# 51.net
KiCad netlist of a schematic drawn in EasyEDA Pro
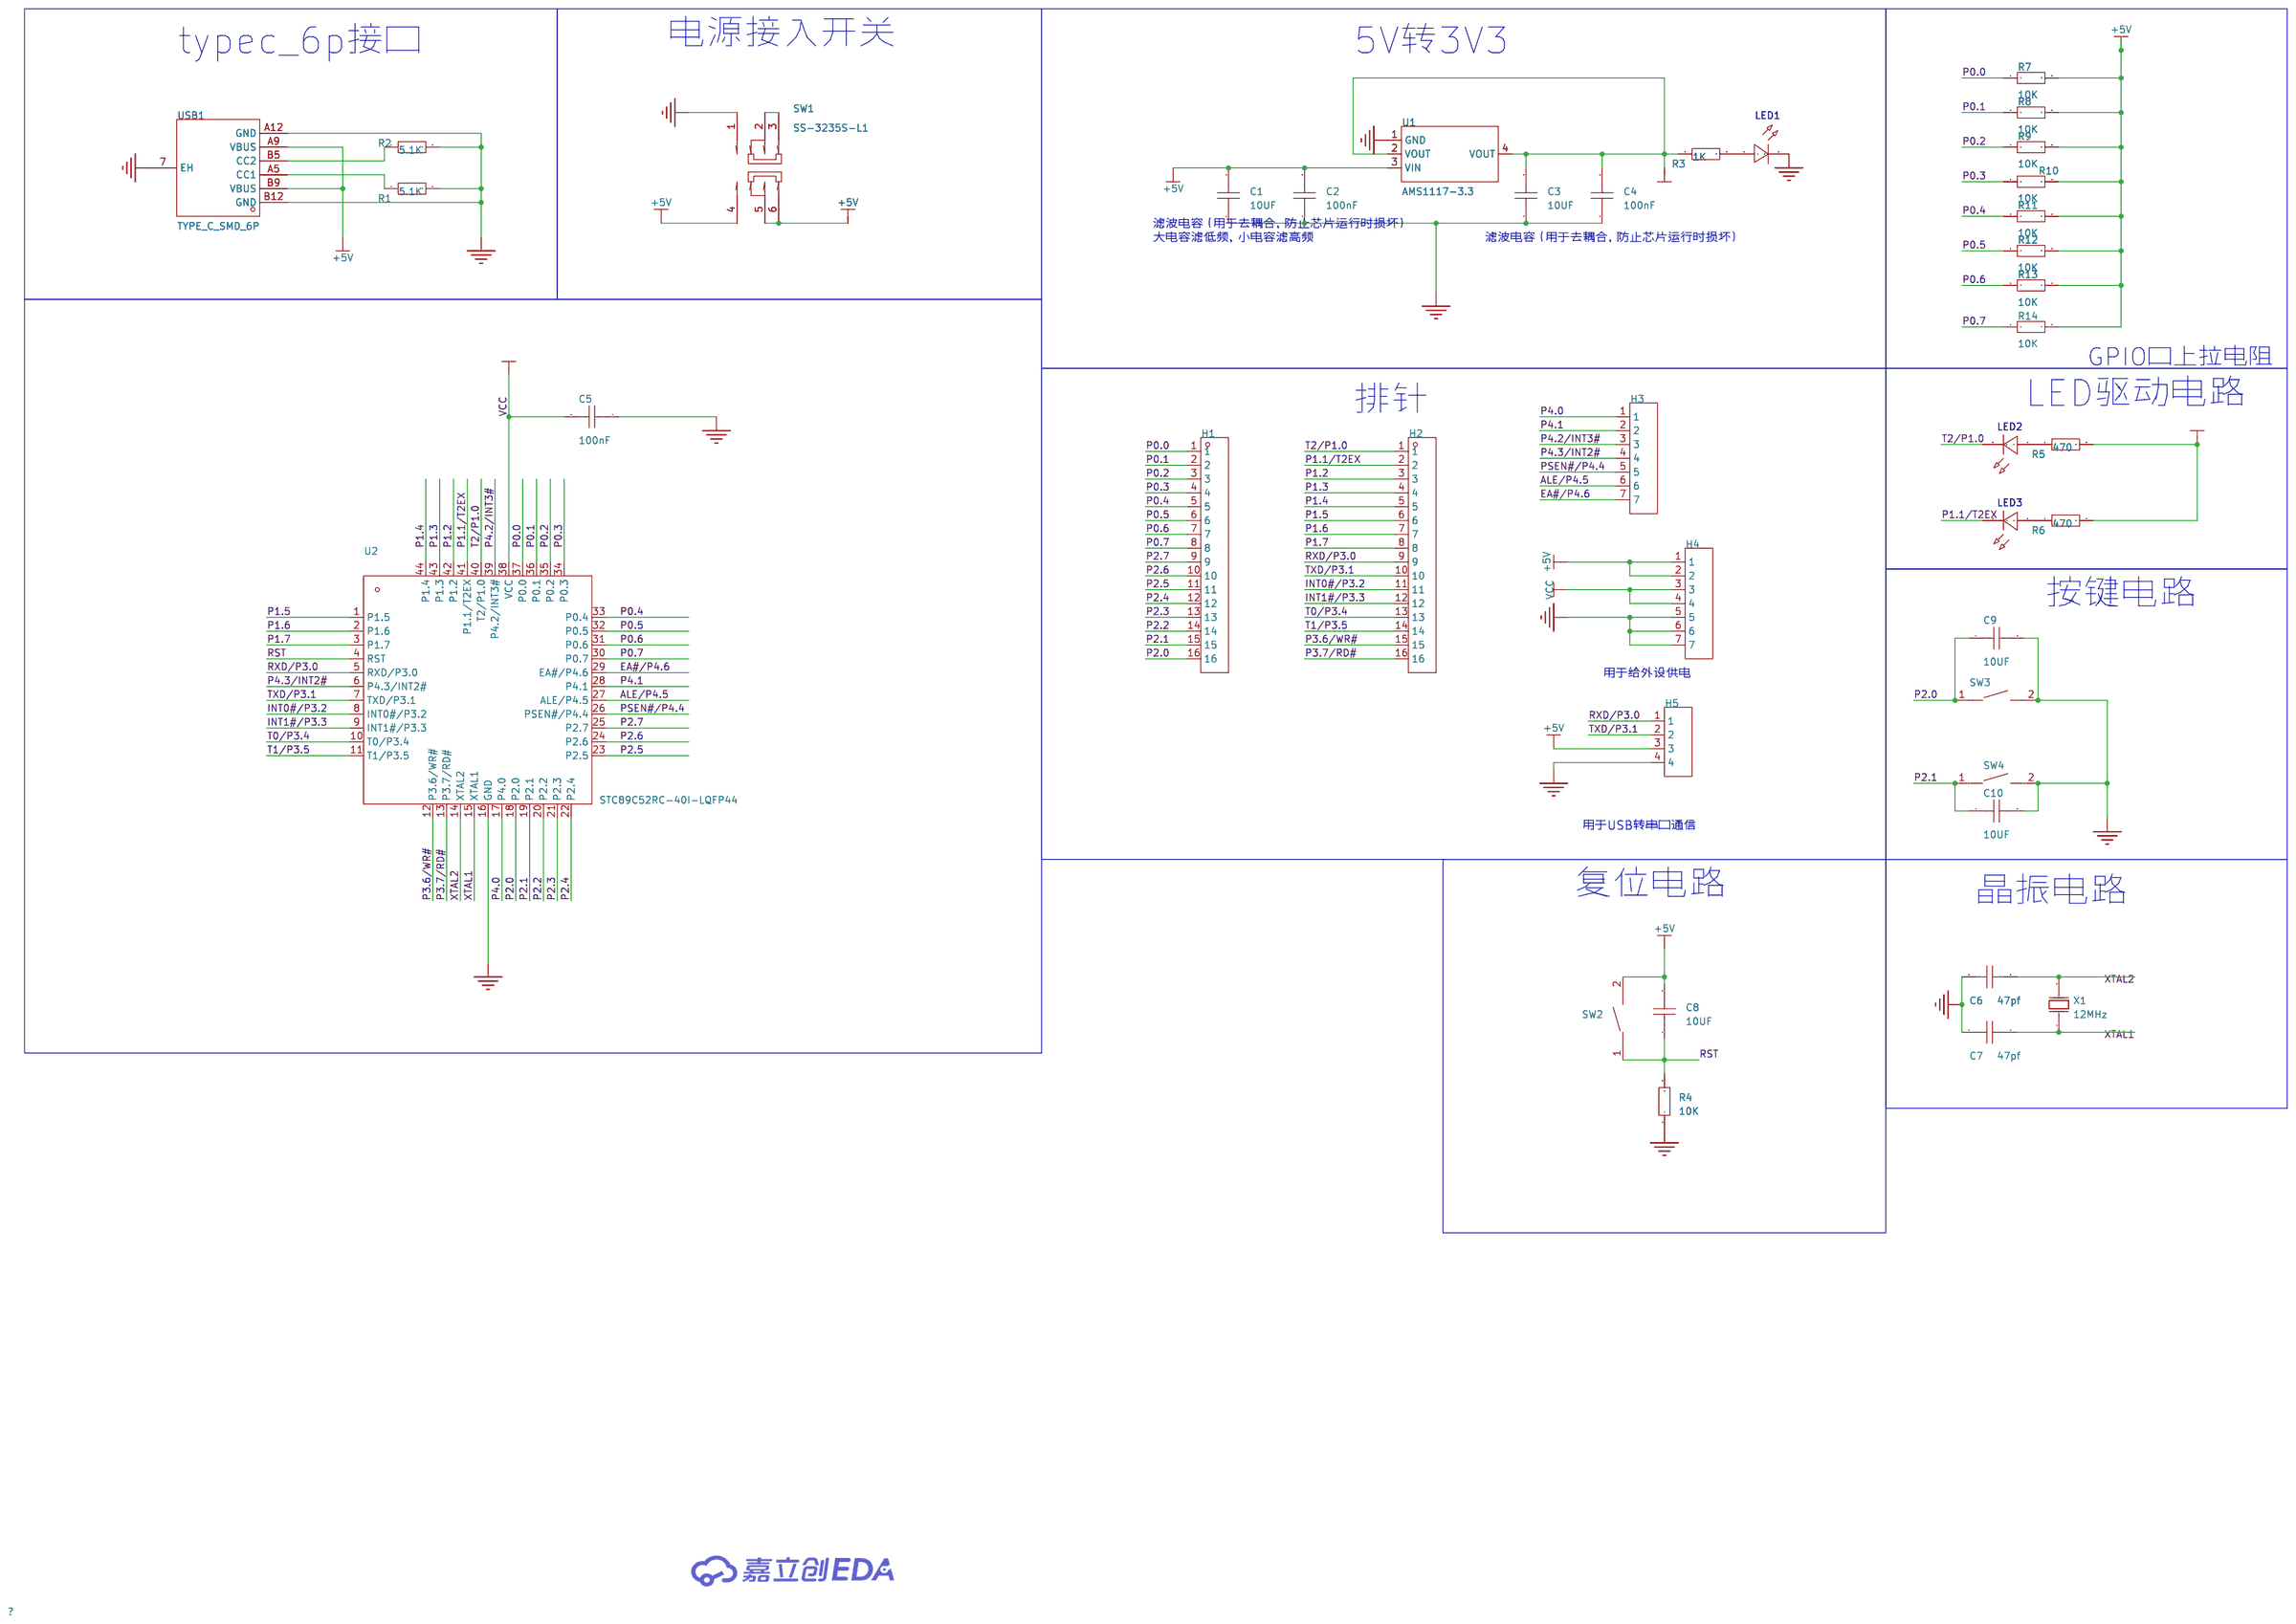
[diagram p0: schematic sheet]

(export (version "E")
  (design (tool "Eeschema 10.0.6"))
  (components
    (comp (ref "C1")
      (value "10UF")
      (footprint "easyedapro:C0805")
      (libsource (lib "easyedapro") (part "CapAcitance"))
    )
    (comp (ref "C2")
      (value "100nF")
      (footprint "easyedapro:C0805")
      (libsource (lib "easyedapro") (part "CapAcitance"))
    )
    (comp (ref "C3")
      (value "10UF")
      (footprint "easyedapro:C0805")
      (libsource (lib "easyedapro") (part "CapAcitance"))
    )
    (comp (ref "C4")
      (value "100nF")
      (footprint "easyedapro:C0805")
      (libsource (lib "easyedapro") (part "CapAcitance"))
    )
    (comp (ref "C5")
      (value "100nF")
      (footprint "easyedapro:C0805")
      (libsource (lib "easyedapro") (part "CapAcitance"))
    )
    (comp (ref "C6")
      (value "47pf")
      (footprint "easyedapro:C0805")
      (libsource (lib "easyedapro") (part "CapAcitance"))
    )
    (comp (ref "C7")
      (value "47pf")
      (footprint "easyedapro:C0805")
      (libsource (lib "easyedapro") (part "CapAcitance"))
    )
    (comp (ref "C8")
      (value "10UF")
      (footprint "easyedapro:C0805")
      (libsource (lib "easyedapro") (part "CapAcitance"))
    )
    (comp (ref "C9")
      (value "10UF")
      (footprint "easyedapro:C0805")
      (libsource (lib "easyedapro") (part "CapAcitance"))
    )
    (comp (ref "C10")
      (value "10UF")
      (footprint "easyedapro:C0805")
      (libsource (lib "easyedapro") (part "CapAcitance"))
    )
    (comp (ref "H1")
      (value "~")
      (footprint "easyedapro:HDR-TH_16P-P2.54-V-M")
      (libsource (lib "easyedapro") (part "HDR_2.54-1x16P"))
    )
    (comp (ref "H2")
      (value "~")
      (footprint "easyedapro:HDR-TH_16P-P2.54-V-M")
      (libsource (lib "easyedapro") (part "HDR_2.54-1x16P"))
    )
    (comp (ref "H3")
      (value "~")
      (footprint "easyedapro:HDR-TH_7P-P2.54-V-M")
      (libsource (lib "easyedapro") (part "PZ254V-11-07P"))
    )
    (comp (ref "H4")
      (value "~")
      (footprint "easyedapro:HDR-TH_7P-P2.54-V-M")
      (libsource (lib "easyedapro") (part "PZ254V-11-07P"))
    )
    (comp (ref "H5")
      (value "~")
      (footprint "easyedapro:HDR-TH_4P-P2.54-V-M")
      (libsource (lib "easyedapro") (part "PZ254V-11-04P"))
    )
    (comp (ref "LED1")
      (value "~")
      (footprint "easyedapro:LED_0805")
      (libsource (lib "easyedapro") (part "LED_G"))
    )
    (comp (ref "LED2")
      (value "~")
      (footprint "easyedapro:LED_0805")
      (libsource (lib "easyedapro") (part "LED_G"))
    )
    (comp (ref "LED3")
      (value "~")
      (footprint "easyedapro:LED_0805")
      (libsource (lib "easyedapro") (part "LED_G"))
    )
    (comp (ref "R1") (value "5.1K") (footprint "easyedapro:R0805") (libsource (lib "easyedapro") (part "电阻")))
    (comp (ref "R2") (value "5.1K") (footprint "easyedapro:R0805") (libsource (lib "easyedapro") (part "电阻")))
    (comp (ref "R3") (value "1K") (footprint "easyedapro:R0805") (libsource (lib "easyedapro") (part "电阻")))
    (comp (ref "R4") (value "10K") (footprint "easyedapro:R0805") (libsource (lib "easyedapro") (part "电阻")))
    (comp (ref "R5") (value "470") (footprint "easyedapro:R0805") (libsource (lib "easyedapro") (part "电阻")))
    (comp (ref "R6") (value "470") (footprint "easyedapro:R0805") (libsource (lib "easyedapro") (part "电阻")))
    (comp (ref "R7") (value "10K") (footprint "easyedapro:R0805") (libsource (lib "easyedapro") (part "电阻")))
    (comp (ref "R8") (value "10K") (footprint "easyedapro:R0805") (libsource (lib "easyedapro") (part "电阻")))
    (comp (ref "R9") (value "10K") (footprint "easyedapro:R0805") (libsource (lib "easyedapro") (part "电阻")))
    (comp (ref "R10") (value "10K") (footprint "easyedapro:R0805") (libsource (lib "easyedapro") (part "电阻")))
    (comp (ref "R11") (value "10K") (footprint "easyedapro:R0805") (libsource (lib "easyedapro") (part "电阻")))
    (comp (ref "R12") (value "10K") (footprint "easyedapro:R0805") (libsource (lib "easyedapro") (part "电阻")))
    (comp (ref "R13") (value "10K") (footprint "easyedapro:R0805") (libsource (lib "easyedapro") (part "电阻")))
    (comp (ref "R14") (value "10K") (footprint "easyedapro:R0805") (libsource (lib "easyedapro") (part "电阻")))
    (comp (ref "SW1")
      (value "SS-3235S-L1")
      (footprint "easyedapro:SW-SMD_SS-3235S-LX")
      (description "电路结构:双刀双掷;安装方式:卧贴;开关颜色:黑色;额定电流(DC):50mA;额定电压(DC):12V;额定电流(AC):50mA;额定电压(AC):12V;机械寿命:1万次;")
      (fields (field (name "Manufacturer") "XKB Connectivity(中国星坤)"))
      (libsource (lib "easyedapro") (part "SS-3235S-L1"))
    )
    (comp (ref "SW2")
      (value "轻触按键3*4*H")
      (footprint "easyedapro:SW-SMD_L4.0-W2.9-LS5.0")
      (libsource (lib "easyedapro") (part "轻触按键3*4*H"))
    )
    (comp (ref "SW3")
      (value "轻触按键3*4*H")
      (footprint "easyedapro:SW-SMD_L4.0-W2.9-LS5.0")
      (libsource (lib "easyedapro") (part "轻触按键3*4*H"))
    )
    (comp (ref "SW4")
      (value "轻触按键3*4*H")
      (footprint "easyedapro:SW-SMD_L4.0-W2.9-LS5.0")
      (libsource (lib "easyedapro") (part "轻触按键3*4*H"))
    )
    (comp (ref "U1")
      (value "AMS1117-3.3")
      (footprint "easyedapro:SOT-223-3_L6.5-W3.4-P2.30-LS7.0-BR")
      (description "输出类型:固定;工作电压:16V;输出电压:3.3V;输出电流:1A;电源纹波抑制比(PSRR):72dB@(120Hz);输出极性:正极;")
      (fields (field (name "Manufacturer") "AMS"))
      (libsource (lib "easyedapro") (part "AMS1117-3.3"))
    )
    (comp (ref "U2")
      (value "STC89C52RC-40I-LQFP44")
      (footprint "easyedapro:LQFP-44_L10.0-W10.0-P0.80-LS12.0-BL")
      (description "CPU内核:51系列;应用领域:-;")
      (fields (field (name "Manufacturer") "STC"))
      (libsource (lib "easyedapro") (part "STC89C52RC-40I_C8707"))
    )
    (comp (ref "USB1")
      (value "TYPE_C_SMD_6P")
      (footprint "easyedapro:TYPE-C-SMD_TYPE-C-6P")
      (libsource (lib "easyedapro") (part "TYPE_C_SMD_6P"))
    )
    (comp (ref "X1")
      (value "12MHz")
      (footprint "easyedapro:CRYSTAL-SMD_L7.0-W4.0-LS7.8")
      (description "频率:12MHz;常温频差:±15ppm;负载电容:20pF;频率稳定度:±30ppm;")
      (fields (field (name "Manufacturer Part") "12M 20PF 15PPM") (field (name "Manufacturer") "SST(索斯特)"))
      (libsource (lib "easyedapro") (part "12M 20PF 15PPM"))
    )
  )
  (nets
    (net (code "1") (name "+5V") (class "Default")
      (node (ref "C1") (pin "2") (pinfunction "2_2") (pintype "input"))
      (node (ref "C2") (pin "2") (pinfunction "2_2") (pintype "input"))
      (node (ref "C8") (pin "2") (pinfunction "2_2") (pintype "input"))
      (node (ref "H4") (pin "1") (pinfunction "1_1") (pintype "unspecified"))
      (node (ref "H4") (pin "2") (pinfunction "2_2") (pintype "unspecified"))
      (node (ref "H5") (pin "3") (pinfunction "3_3") (pintype "unspecified"))
      (node (ref "R10") (pin "2") (pinfunction "2_2") (pintype "input"))
      (node (ref "R11") (pin "2") (pinfunction "2_2") (pintype "input"))
      (node (ref "R12") (pin "2") (pinfunction "2_2") (pintype "input"))
      (node (ref "R13") (pin "2") (pinfunction "2_2") (pintype "input"))
      (node (ref "R14") (pin "2") (pinfunction "2_2") (pintype "input"))
      (node (ref "R7") (pin "2") (pinfunction "2_2") (pintype "input"))
      (node (ref "R8") (pin "2") (pinfunction "2_2") (pintype "input"))
      (node (ref "R9") (pin "2") (pinfunction "2_2") (pintype "input"))
      (node (ref "SW1") (pin "4") (pinfunction "4_4") (pintype "unspecified"))
      (node (ref "SW1") (pin "5") (pinfunction "5_5") (pintype "unspecified"))
      (node (ref "SW1") (pin "6") (pinfunction "6_6") (pintype "unspecified"))
      (node (ref "SW2") (pin "2") (pinfunction "2_2") (pintype "unspecified"))
      (node (ref "U1") (pin "3") (pinfunction "VIN_3") (pintype "unspecified"))
      (node (ref "USB1") (pin "A9") (pinfunction "VBUS_A9") (pintype "unspecified"))
      (node (ref "USB1") (pin "B9") (pinfunction "VBUS_B9") (pintype "unspecified"))
    )
    (net (code "2") (name "/ALE{slash}P4.5") (class "Default")
      (node (ref "H3") (pin "6") (pinfunction "6_6") (pintype "unspecified"))
      (node (ref "U2") (pin "27") (pinfunction "ALE/P4.5_27") (pintype "unspecified"))
    )
    (net (code "3") (name "/EA#{slash}P4.6") (class "Default")
      (node (ref "H3") (pin "7") (pinfunction "7_7") (pintype "unspecified"))
      (node (ref "U2") (pin "29") (pinfunction "EA#/P4.6_29") (pintype "unspecified"))
    )
    (net (code "4") (name "/INT0#{slash}P3.2") (class "Default")
      (node (ref "H2") (pin "11") (pinfunction "11_11") (pintype "input"))
      (node (ref "U2") (pin "8") (pinfunction "INT0#/P3.2_8") (pintype "unspecified"))
    )
    (net (code "5") (name "/INT1#{slash}P3.3") (class "Default")
      (node (ref "H2") (pin "12") (pinfunction "12_12") (pintype "input"))
      (node (ref "U2") (pin "9") (pinfunction "INT1#/P3.3_9") (pintype "unspecified"))
    )
    (net (code "6") (name "/P0.0") (class "Default")
      (node (ref "H1") (pin "1") (pinfunction "1_1") (pintype "input"))
      (node (ref "R7") (pin "1") (pinfunction "1_1") (pintype "input"))
      (node (ref "U2") (pin "37") (pinfunction "P0.0_37") (pintype "unspecified"))
    )
    (net (code "7") (name "/P0.1") (class "Default")
      (node (ref "H1") (pin "2") (pinfunction "2_2") (pintype "input"))
      (node (ref "R8") (pin "1") (pinfunction "1_1") (pintype "input"))
      (node (ref "U2") (pin "36") (pinfunction "P0.1_36") (pintype "unspecified"))
    )
    (net (code "8") (name "/P0.2") (class "Default")
      (node (ref "H1") (pin "3") (pinfunction "3_3") (pintype "input"))
      (node (ref "R9") (pin "1") (pinfunction "1_1") (pintype "input"))
      (node (ref "U2") (pin "35") (pinfunction "P0.2_35") (pintype "unspecified"))
    )
    (net (code "9") (name "/P0.3") (class "Default")
      (node (ref "H1") (pin "4") (pinfunction "4_4") (pintype "input"))
      (node (ref "R10") (pin "1") (pinfunction "1_1") (pintype "input"))
      (node (ref "U2") (pin "34") (pinfunction "P0.3_34") (pintype "unspecified"))
    )
    (net (code "10") (name "/P0.4") (class "Default")
      (node (ref "H1") (pin "5") (pinfunction "5_5") (pintype "input"))
      (node (ref "R11") (pin "1") (pinfunction "1_1") (pintype "input"))
      (node (ref "U2") (pin "33") (pinfunction "P0.4_33") (pintype "unspecified"))
    )
    (net (code "11") (name "/P0.5") (class "Default")
      (node (ref "H1") (pin "6") (pinfunction "6_6") (pintype "input"))
      (node (ref "R12") (pin "1") (pinfunction "1_1") (pintype "input"))
      (node (ref "U2") (pin "32") (pinfunction "P0.5_32") (pintype "unspecified"))
    )
    (net (code "12") (name "/P0.6") (class "Default")
      (node (ref "H1") (pin "7") (pinfunction "7_7") (pintype "input"))
      (node (ref "R13") (pin "1") (pinfunction "1_1") (pintype "input"))
      (node (ref "U2") (pin "31") (pinfunction "P0.6_31") (pintype "unspecified"))
    )
    (net (code "13") (name "/P0.7") (class "Default")
      (node (ref "H1") (pin "8") (pinfunction "8_8") (pintype "input"))
      (node (ref "R14") (pin "1") (pinfunction "1_1") (pintype "input"))
      (node (ref "U2") (pin "30") (pinfunction "P0.7_30") (pintype "unspecified"))
    )
    (net (code "14") (name "/P1.1{slash}T2EX") (class "Default")
      (node (ref "H2") (pin "2") (pinfunction "2_2") (pintype "input"))
      (node (ref "LED3") (pin "1") (pinfunction "C_1") (pintype "input"))
      (node (ref "U2") (pin "41") (pinfunction "P1.1/T2EX_41") (pintype "unspecified"))
    )
    (net (code "15") (name "/P1.2") (class "Default")
      (node (ref "H2") (pin "3") (pinfunction "3_3") (pintype "input"))
      (node (ref "U2") (pin "42") (pinfunction "P1.2_42") (pintype "unspecified"))
    )
    (net (code "16") (name "/P1.3") (class "Default")
      (node (ref "H2") (pin "4") (pinfunction "4_4") (pintype "input"))
      (node (ref "U2") (pin "43") (pinfunction "P1.3_43") (pintype "unspecified"))
    )
    (net (code "17") (name "/P1.4") (class "Default")
      (node (ref "H2") (pin "5") (pinfunction "5_5") (pintype "input"))
      (node (ref "U2") (pin "44") (pinfunction "P1.4_44") (pintype "unspecified"))
    )
    (net (code "18") (name "/P1.5") (class "Default")
      (node (ref "H2") (pin "6") (pinfunction "6_6") (pintype "input"))
      (node (ref "U2") (pin "1") (pinfunction "P1.5_1") (pintype "unspecified"))
    )
    (net (code "19") (name "/P1.6") (class "Default")
      (node (ref "H2") (pin "7") (pinfunction "7_7") (pintype "input"))
      (node (ref "U2") (pin "2") (pinfunction "P1.6_2") (pintype "unspecified"))
    )
    (net (code "20") (name "/P1.7") (class "Default")
      (node (ref "H2") (pin "8") (pinfunction "8_8") (pintype "input"))
      (node (ref "U2") (pin "3") (pinfunction "P1.7_3") (pintype "unspecified"))
    )
    (net (code "21") (name "/P2.0") (class "Default")
      (node (ref "C9") (pin "1") (pinfunction "1_1") (pintype "input"))
      (node (ref "H1") (pin "16") (pinfunction "16_16") (pintype "input"))
      (node (ref "SW3") (pin "1") (pinfunction "1_1") (pintype "unspecified"))
      (node (ref "U2") (pin "18") (pinfunction "P2.0_18") (pintype "unspecified"))
    )
    (net (code "22") (name "/P2.1") (class "Default")
      (node (ref "C10") (pin "1") (pinfunction "1_1") (pintype "input"))
      (node (ref "H1") (pin "15") (pinfunction "15_15") (pintype "input"))
      (node (ref "SW4") (pin "1") (pinfunction "1_1") (pintype "unspecified"))
      (node (ref "U2") (pin "19") (pinfunction "P2.1_19") (pintype "unspecified"))
    )
    (net (code "23") (name "/P2.2") (class "Default")
      (node (ref "H1") (pin "14") (pinfunction "14_14") (pintype "input"))
      (node (ref "U2") (pin "20") (pinfunction "P2.2_20") (pintype "unspecified"))
    )
    (net (code "24") (name "/P2.3") (class "Default")
      (node (ref "H1") (pin "13") (pinfunction "13_13") (pintype "input"))
      (node (ref "U2") (pin "21") (pinfunction "P2.3_21") (pintype "unspecified"))
    )
    (net (code "25") (name "/P2.4") (class "Default")
      (node (ref "H1") (pin "12") (pinfunction "12_12") (pintype "input"))
      (node (ref "U2") (pin "22") (pinfunction "P2.4_22") (pintype "unspecified"))
    )
    (net (code "26") (name "/P2.5") (class "Default")
      (node (ref "H1") (pin "11") (pinfunction "11_11") (pintype "input"))
      (node (ref "U2") (pin "23") (pinfunction "P2.5_23") (pintype "unspecified"))
    )
    (net (code "27") (name "/P2.6") (class "Default")
      (node (ref "H1") (pin "10") (pinfunction "10_10") (pintype "input"))
      (node (ref "U2") (pin "24") (pinfunction "P2.6_24") (pintype "unspecified"))
    )
    (net (code "28") (name "/P2.7") (class "Default")
      (node (ref "H1") (pin "9") (pinfunction "9_9") (pintype "input"))
      (node (ref "U2") (pin "25") (pinfunction "P2.7_25") (pintype "unspecified"))
    )
    (net (code "29") (name "/P3.6{slash}WR#") (class "Default")
      (node (ref "H2") (pin "15") (pinfunction "15_15") (pintype "input"))
      (node (ref "U2") (pin "12") (pinfunction "P3.6/WR#_12") (pintype "unspecified"))
    )
    (net (code "30") (name "/P3.7{slash}RD#") (class "Default")
      (node (ref "H2") (pin "16") (pinfunction "16_16") (pintype "input"))
      (node (ref "U2") (pin "13") (pinfunction "P3.7/RD#_13") (pintype "unspecified"))
    )
    (net (code "31") (name "/P4.0") (class "Default")
      (node (ref "H3") (pin "1") (pinfunction "1_1") (pintype "unspecified"))
      (node (ref "U2") (pin "17") (pinfunction "P4.0_17") (pintype "unspecified"))
    )
    (net (code "32") (name "/P4.1") (class "Default")
      (node (ref "H3") (pin "2") (pinfunction "2_2") (pintype "unspecified"))
      (node (ref "U2") (pin "28") (pinfunction "P4.1_28") (pintype "unspecified"))
    )
    (net (code "33") (name "/P4.2{slash}INT3#") (class "Default")
      (node (ref "H3") (pin "3") (pinfunction "3_3") (pintype "unspecified"))
      (node (ref "U2") (pin "39") (pinfunction "P4.2/INT3#_39") (pintype "unspecified"))
    )
    (net (code "34") (name "/P4.3{slash}INT2#") (class "Default")
      (node (ref "H3") (pin "4") (pinfunction "4_4") (pintype "unspecified"))
      (node (ref "U2") (pin "6") (pinfunction "P4.3/INT2#_6") (pintype "unspecified"))
    )
    (net (code "35") (name "/PSEN#{slash}P4.4") (class "Default")
      (node (ref "H3") (pin "5") (pinfunction "5_5") (pintype "unspecified"))
      (node (ref "U2") (pin "26") (pinfunction "PSEN#/P4.4_26") (pintype "unspecified"))
    )
    (net (code "36") (name "/RST") (class "Default")
      (node (ref "C8") (pin "1") (pinfunction "1_1") (pintype "input"))
      (node (ref "R4") (pin "2") (pinfunction "2_2") (pintype "input"))
      (node (ref "SW2") (pin "1") (pinfunction "1_1") (pintype "unspecified"))
      (node (ref "U2") (pin "4") (pinfunction "RST_4") (pintype "unspecified"))
    )
    (net (code "37") (name "/RXD{slash}P3.0") (class "Default")
      (node (ref "H2") (pin "9") (pinfunction "9_9") (pintype "input"))
      (node (ref "H5") (pin "1") (pinfunction "1_1") (pintype "unspecified"))
      (node (ref "U2") (pin "5") (pinfunction "RXD/P3.0_5") (pintype "unspecified"))
    )
    (net (code "38") (name "/T0{slash}P3.4") (class "Default")
      (node (ref "H2") (pin "13") (pinfunction "13_13") (pintype "input"))
      (node (ref "U2") (pin "10") (pinfunction "T0/P3.4_10") (pintype "unspecified"))
    )
    (net (code "39") (name "/T1{slash}P3.5") (class "Default")
      (node (ref "H2") (pin "14") (pinfunction "14_14") (pintype "input"))
      (node (ref "U2") (pin "11") (pinfunction "T1/P3.5_11") (pintype "unspecified"))
    )
    (net (code "40") (name "/T2{slash}P1.0") (class "Default")
      (node (ref "H2") (pin "1") (pinfunction "1_1") (pintype "input"))
      (node (ref "LED2") (pin "1") (pinfunction "C_1") (pintype "input"))
      (node (ref "U2") (pin "40") (pinfunction "T2/P1.0_40") (pintype "unspecified"))
    )
    (net (code "41") (name "/TXD{slash}P3.1") (class "Default")
      (node (ref "H2") (pin "10") (pinfunction "10_10") (pintype "input"))
      (node (ref "H5") (pin "2") (pinfunction "2_2") (pintype "unspecified"))
      (node (ref "U2") (pin "7") (pinfunction "TXD/P3.1_7") (pintype "unspecified"))
    )
    (net (code "42") (name "/XTAL1") (class "Default")
      (node (ref "C7") (pin "2") (pinfunction "2_2") (pintype "input"))
      (node (ref "U2") (pin "15") (pinfunction "XTAL1_15") (pintype "unspecified"))
      (node (ref "X1") (pin "1") (pinfunction "OSC1_1") (pintype "input"))
    )
    (net (code "43") (name "/XTAL2") (class "Default")
      (node (ref "C6") (pin "2") (pinfunction "2_2") (pintype "input"))
      (node (ref "U2") (pin "14") (pinfunction "XTAL2_14") (pintype "unspecified"))
      (node (ref "X1") (pin "2") (pinfunction "OSC2_2") (pintype "input"))
    )
    (net (code "44") (name "3V3") (class "Default")
      (node (ref "C3") (pin "2") (pinfunction "2_2") (pintype "input"))
      (node (ref "C4") (pin "2") (pinfunction "2_2") (pintype "input"))
      (node (ref "R3") (pin "1") (pinfunction "1_1") (pintype "input"))
      (node (ref "R5") (pin "2") (pinfunction "2_2") (pintype "input"))
      (node (ref "R6") (pin "2") (pinfunction "2_2") (pintype "input"))
      (node (ref "U1") (pin "2") (pinfunction "VOUT_2") (pintype "unspecified"))
      (node (ref "U1") (pin "4") (pinfunction "VOUT_4") (pintype "unspecified"))
    )
    (net (code "45") (name "GND") (class "Default")
      (node (ref "C1") (pin "1") (pinfunction "1_1") (pintype "input"))
      (node (ref "C10") (pin "2") (pinfunction "2_2") (pintype "input"))
      (node (ref "C2") (pin "1") (pinfunction "1_1") (pintype "input"))
      (node (ref "C3") (pin "1") (pinfunction "1_1") (pintype "input"))
      (node (ref "C4") (pin "1") (pinfunction "1_1") (pintype "input"))
      (node (ref "C5") (pin "1") (pinfunction "1_1") (pintype "input"))
      (node (ref "C6") (pin "1") (pinfunction "1_1") (pintype "input"))
      (node (ref "C7") (pin "1") (pinfunction "1_1") (pintype "input"))
      (node (ref "C9") (pin "2") (pinfunction "2_2") (pintype "input"))
      (node (ref "H4") (pin "5") (pinfunction "5_5") (pintype "unspecified"))
      (node (ref "H4") (pin "6") (pinfunction "6_6") (pintype "unspecified"))
      (node (ref "H4") (pin "7") (pinfunction "7_7") (pintype "unspecified"))
      (node (ref "H5") (pin "4") (pinfunction "4_4") (pintype "unspecified"))
      (node (ref "LED1") (pin "1") (pinfunction "C_1") (pintype "input"))
      (node (ref "R1") (pin "2") (pinfunction "2_2") (pintype "input"))
      (node (ref "R2") (pin "2") (pinfunction "2_2") (pintype "input"))
      (node (ref "R4") (pin "1") (pinfunction "1_1") (pintype "input"))
      (node (ref "SW1") (pin "1") (pinfunction "1_1") (pintype "unspecified"))
      (node (ref "SW3") (pin "2") (pinfunction "2_2") (pintype "unspecified"))
      (node (ref "SW4") (pin "2") (pinfunction "2_2") (pintype "unspecified"))
      (node (ref "U1") (pin "1") (pinfunction "GND_1") (pintype "unspecified"))
      (node (ref "U2") (pin "16") (pinfunction "GND_16") (pintype "unspecified"))
      (node (ref "USB1") (pin "7") (pinfunction "EH_7") (pintype "unspecified"))
      (node (ref "USB1") (pin "A12") (pinfunction "GND_A12") (pintype "unspecified"))
      (node (ref "USB1") (pin "B12") (pinfunction "GND_B12") (pintype "unspecified"))
    )
    (net (code "46") (name "Net-(LED1-A)") (class "Default")
      (node (ref "LED1") (pin "2") (pinfunction "A_2") (pintype "input"))
      (node (ref "R3") (pin "2") (pinfunction "2_2") (pintype "input"))
    )
    (net (code "47") (name "Net-(LED2-A)") (class "Default")
      (node (ref "LED2") (pin "2") (pinfunction "A_2") (pintype "input"))
      (node (ref "R5") (pin "1") (pinfunction "1_1") (pintype "input"))
    )
    (net (code "48") (name "Net-(LED3-A)") (class "Default")
      (node (ref "LED3") (pin "2") (pinfunction "A_2") (pintype "input"))
      (node (ref "R6") (pin "1") (pinfunction "1_1") (pintype "input"))
    )
    (net (code "49") (name "Net-(SW1-Pad2)") (class "Default")
      (node (ref "SW1") (pin "2") (pinfunction "2_2") (pintype "unspecified"))
      (node (ref "SW1") (pin "3") (pinfunction "3_3") (pintype "unspecified"))
    )
    (net (code "50") (name "Net-(USB1-CC1)") (class "Default")
      (node (ref "R1") (pin "1") (pinfunction "1_1") (pintype "input"))
      (node (ref "USB1") (pin "A5") (pinfunction "CC1_A5") (pintype "unspecified"))
    )
    (net (code "51") (name "Net-(USB1-CC2)") (class "Default")
      (node (ref "R2") (pin "1") (pinfunction "1_1") (pintype "input"))
      (node (ref "USB1") (pin "B5") (pinfunction "CC2_B5") (pintype "unspecified"))
    )
    (net (code "52") (name "VCC") (class "Default")
      (node (ref "C5") (pin "2") (pinfunction "2_2") (pintype "input"))
      (node (ref "H4") (pin "3") (pinfunction "3_3") (pintype "unspecified"))
      (node (ref "H4") (pin "4") (pinfunction "4_4") (pintype "unspecified"))
      (node (ref "U2") (pin "38") (pinfunction "VCC_38") (pintype "unspecified"))
    )
  )
)
